# LCD.net
KiCad netlist of a schematic drawn in Altium Designer
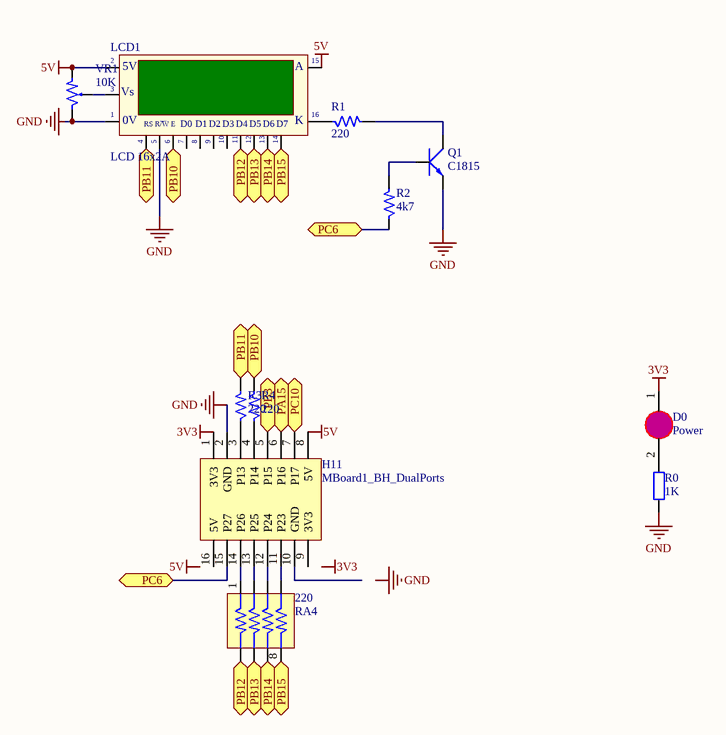
[diagram p0: LCD.SchDoc]

(export (version "E")
  (design (tool "Eeschema 10.0.6"))
  (components
    (comp (ref "220") (value "RA4") (footprint "RA4") (libsource (lib "Nhat_Lib") (part "RA4")))
    (comp (ref "D0")
      (value "Power")
      (footprint "SMD0805")
      (description "LED 3mm")
      (libsource (lib "minhLIB") (part "LEDSMD"))
    )
    (comp (ref "H11")
      (value "MBoard1_BH_DualPorts")
      (footprint "MBoard1_BH_DualPorts")
      (libsource (lib "Nhat_Lib") (part "MBoard1_BH_DualPorts"))
    )
    (comp (ref "LCD1")
      (value "LCD 16x2A")
      (footprint "LCD16X2")
      (description "LCD dipslay 16 char, 2 line")
      (libsource (lib "minhLIB") (part "LCD16x2A"))
    )
    (comp (ref "Q1")
      (value "C1815")
      (footprint "SOT23B")
      (description "NPN 600mW, ECB")
      (libsource (lib "VioletofSun") (part "C1815"))
    )
    (comp (ref "R0")
      (value "1K")
      (footprint "SMD0805R")
      (description "RES_08")
      (fields (field (name "Comment") "R") (field (name "PUBLISHER") "Altium Limited"))
      (libsource (lib "minhLIB") (part "R"))
    )
    (comp (ref "R1")
      (value "220")
      (footprint "minhLIB:SMD0805R")
      (description "Resistor 1/4W")
      (libsource (lib "VioletofSun") (part "R"))
    )
    (comp (ref "R2")
      (value "4k7")
      (footprint "minhLIB:SMD0805R")
      (description "Resistor 1/4W")
      (libsource (lib "VioletofSun") (part "R"))
    )
    (comp (ref "R3")
      (value "220")
      (footprint "minhLIB:SMD0805R")
      (description "Resistor 1/4W")
      (libsource (lib "syhaunguyen") (part "R"))
    )
    (comp (ref "R4")
      (value "220")
      (footprint "minhLIB:SMD0805R")
      (description "Resistor 1/4W")
      (libsource (lib "syhaunguyen") (part "R"))
    )
    (comp (ref "VR1")
      (value "10K")
      (footprint "VR1")
      (description "Var Resistor")
      (libsource (lib "VioletofSun") (part "VR1"))
    )
  )
  (nets
    (net (code "1") (name "/PA15") (class "Default")
      (node (ref "H11") (pin "6") (pinfunction "P16_6") (pintype "passive"))
    )
    (net (code "2") (name "/PB3") (class "Default")
      (node (ref "H11") (pin "5") (pinfunction "P15_5") (pintype "passive"))
    )
    (net (code "3") (name "/PB10") (class "Default")
      (node (ref "LCD1") (pin "6") (pinfunction "~{EN}_6") (pintype "passive"))
      (node (ref "R4") (pin "2") (pinfunction "2_2") (pintype "passive"))
    )
    (net (code "4") (name "/PB11") (class "Default")
      (node (ref "LCD1") (pin "4") (pinfunction "RS_4") (pintype "passive"))
      (node (ref "R3") (pin "2") (pinfunction "2_2") (pintype "passive"))
    )
    (net (code "5") (name "/PB12") (class "Default")
      (node (ref "220") (pin "2") (pinfunction "2_2") (pintype "passive"))
      (node (ref "LCD1") (pin "11") (pinfunction "D4_11") (pintype "passive"))
    )
    (net (code "6") (name "/PB13") (class "Default")
      (node (ref "220") (pin "4") (pinfunction "4_4") (pintype "passive"))
      (node (ref "LCD1") (pin "12") (pinfunction "D5_12") (pintype "passive"))
    )
    (net (code "7") (name "/PB14") (class "Default")
      (node (ref "220") (pin "6") (pinfunction "6_6") (pintype "passive"))
      (node (ref "LCD1") (pin "13") (pinfunction "D6_13") (pintype "passive"))
    )
    (net (code "8") (name "/PB15") (class "Default")
      (node (ref "220") (pin "8") (pinfunction "8_8") (pintype "passive"))
      (node (ref "LCD1") (pin "14") (pinfunction "D7_14") (pintype "passive"))
    )
    (net (code "9") (name "/PC6") (class "Default")
      (node (ref "H11") (pin "15") (pinfunction "P27_15") (pintype "passive"))
      (node (ref "R2") (pin "1") (pinfunction "1_1") (pintype "passive"))
    )
    (net (code "10") (name "/PC10") (class "Default")
      (node (ref "H11") (pin "7") (pinfunction "P17_7") (pintype "passive"))
    )
    (net (code "11") (name "3V3") (class "Default")
      (node (ref "D0") (pin "1") (pinfunction "A_1") (pintype "passive"))
      (node (ref "H11") (pin "1") (pinfunction "3V3_1") (pintype "passive"))
    )
    (net (code "12") (name "5V") (class "Default")
      (node (ref "H11") (pin "8") (pinfunction "5V_8") (pintype "passive"))
      (node (ref "LCD1") (pin "15") (pinfunction "A_15") (pintype "passive"))
      (node (ref "LCD1") (pin "2") (pinfunction "VDD_2") (pintype "passive"))
      (node (ref "VR1") (pin "1") (pinfunction "1_1") (pintype "passive"))
    )
    (net (code "13") (name "GND") (class "Default")
      (node (ref "H11") (pin "2") (pinfunction "GND_2") (pintype "passive"))
      (node (ref "LCD1") (pin "1") (pinfunction "GND_1") (pintype "passive"))
      (node (ref "LCD1") (pin "5") (pinfunction "R/~{W}_5") (pintype "passive"))
      (node (ref "Q1") (pin "1") (pinfunction "E_1") (pintype "passive"))
      (node (ref "R0") (pin "1") (pinfunction "1_1") (pintype "passive"))
      (node (ref "VR1") (pin "3") (pinfunction "3_3") (pintype "passive"))
    )
    (net (code "14") (name "Net-(D0-K)") (class "Default")
      (node (ref "D0") (pin "2") (pinfunction "K_2") (pintype "passive"))
      (node (ref "R0") (pin "2") (pinfunction "2_2") (pintype "passive"))
    )
    (net (code "15") (name "Net-(H11-P13)") (class "Default")
      (node (ref "H11") (pin "3") (pinfunction "P13_3") (pintype "passive"))
      (node (ref "R3") (pin "1") (pinfunction "1_1") (pintype "passive"))
    )
    (net (code "16") (name "Net-(H11-P14)") (class "Default")
      (node (ref "H11") (pin "4") (pinfunction "P14_4") (pintype "passive"))
      (node (ref "R4") (pin "1") (pinfunction "1_1") (pintype "passive"))
    )
    (net (code "17") (name "Net-(H11-P23)") (class "Default")
      (node (ref "220") (pin "7") (pinfunction "7_7") (pintype "passive"))
      (node (ref "H11") (pin "11") (pinfunction "P23_11") (pintype "passive"))
    )
    (net (code "18") (name "Net-(H11-P24)") (class "Default")
      (node (ref "220") (pin "5") (pinfunction "5_5") (pintype "passive"))
      (node (ref "H11") (pin "12") (pinfunction "P24_12") (pintype "passive"))
    )
    (net (code "19") (name "Net-(H11-P25)") (class "Default")
      (node (ref "220") (pin "3") (pinfunction "3_3") (pintype "passive"))
      (node (ref "H11") (pin "13") (pinfunction "P25_13") (pintype "passive"))
    )
    (net (code "20") (name "Net-(H11-P26)") (class "Default")
      (node (ref "220") (pin "1") (pinfunction "1_1") (pintype "passive"))
      (node (ref "H11") (pin "14") (pinfunction "P26_14") (pintype "passive"))
    )
    (net (code "21") (name "Net-(LCD1-K)") (class "Default")
      (node (ref "LCD1") (pin "16") (pinfunction "K_16") (pintype "passive"))
      (node (ref "R1") (pin "1") (pinfunction "1_1") (pintype "passive"))
    )
    (net (code "22") (name "Net-(LCD1-VEE)") (class "Default")
      (node (ref "LCD1") (pin "3") (pinfunction "VEE_3") (pintype "passive"))
      (node (ref "VR1") (pin "2") (pinfunction "2_2") (pintype "passive"))
    )
    (net (code "23") (name "Net-(Q1-B)") (class "Default")
      (node (ref "Q1") (pin "3") (pinfunction "B_3") (pintype "passive"))
      (node (ref "R2") (pin "2") (pinfunction "2_2") (pintype "passive"))
    )
    (net (code "24") (name "Net-(Q1-C)") (class "Default")
      (node (ref "Q1") (pin "2") (pinfunction "C_2") (pintype "passive"))
      (node (ref "R1") (pin "2") (pinfunction "2_2") (pintype "passive"))
    )
    (net (code "25") (name "unconnected-(H11-3V3-Pad9)") (class "Default")
      (node (ref "H11") (pin "9") (pinfunction "3V3_9") (pintype "passive"))
    )
    (net (code "26") (name "unconnected-(H11-5V-Pad16)") (class "Default")
      (node (ref "H11") (pin "16") (pinfunction "5V_16") (pintype "passive"))
    )
    (net (code "27") (name "unconnected-(H11-GND-Pad10)") (class "Default")
      (node (ref "H11") (pin "10") (pinfunction "GND_10") (pintype "passive"))
    )
    (net (code "28") (name "unconnected-(LCD1-D0-Pad7)") (class "Default")
      (node (ref "LCD1") (pin "7") (pinfunction "D0_7") (pintype "passive"))
    )
    (net (code "29") (name "unconnected-(LCD1-D1-Pad8)") (class "Default")
      (node (ref "LCD1") (pin "8") (pinfunction "D1_8") (pintype "passive"))
    )
    (net (code "30") (name "unconnected-(LCD1-D2-Pad9)") (class "Default")
      (node (ref "LCD1") (pin "9") (pinfunction "D2_9") (pintype "passive"))
    )
    (net (code "31") (name "unconnected-(LCD1-D3-Pad10)") (class "Default")
      (node (ref "LCD1") (pin "10") (pinfunction "D3_10") (pintype "passive"))
    )
  )
)
